# ArticulatedPCBContactBoard.net
KiCad netlist of a schematic drawn in EAGLE
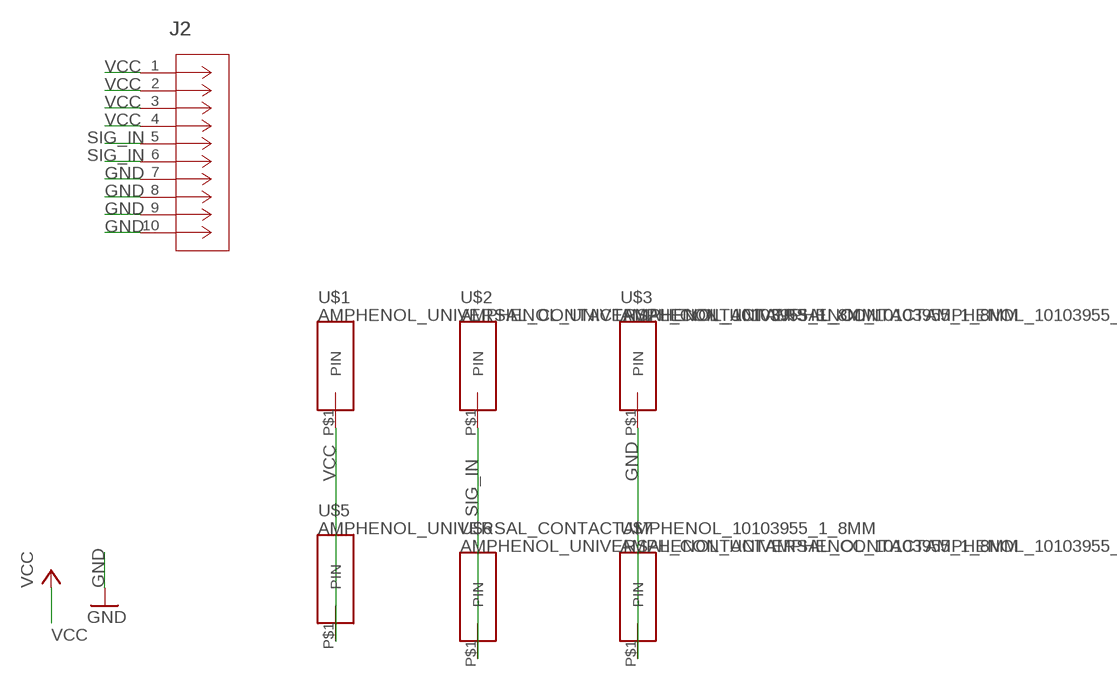
[diagram p0: schematic, sheet 1]

(export (version "E")
  (design (tool "Eeschema 10.0.6"))
  (components
    (comp (ref "J2")
      (value "DF23C-10DS-0.5V(51)")
      (footprint "eagle-import:CONN_DF23C-10DS-0.5V(51)_HIR")
      (fields (field (name "COPYRIGHT") "Copyright (C) 2018 Accelerated Designs. All rights reserved"))
      (libsource (lib "eagle-import") (part "DF23C-10DS-0.5V(51)"))
    )
    (comp (ref "U$1")
      (value "AMPHENOL_UNIVERSAL_CONTACTAMPHENOL_10103955_1_8MM")
      (footprint "eagle-import:AMPHENOL10103955")
      (libsource (lib "eagle-import") (part "AMPHENOL_UNIVERSAL_CONTACTAMPHENOL_10103955_1_8MM"))
    )
    (comp (ref "U$2")
      (value "AMPHENOL_UNIVERSAL_CONTACTAMPHENOL_10103955_1_8MM")
      (footprint "eagle-import:AMPHENOL10103955")
      (libsource (lib "eagle-import") (part "AMPHENOL_UNIVERSAL_CONTACTAMPHENOL_10103955_1_8MM"))
    )
    (comp (ref "U$3")
      (value "AMPHENOL_UNIVERSAL_CONTACTAMPHENOL_10103955_1_8MM")
      (footprint "eagle-import:AMPHENOL10103955")
      (libsource (lib "eagle-import") (part "AMPHENOL_UNIVERSAL_CONTACTAMPHENOL_10103955_1_8MM"))
    )
    (comp (ref "U$5")
      (value "AMPHENOL_UNIVERSAL_CONTACTAMPHENOL_10103955_1_8MM")
      (footprint "eagle-import:AMPHENOL10103955")
      (libsource (lib "eagle-import") (part "AMPHENOL_UNIVERSAL_CONTACTAMPHENOL_10103955_1_8MM"))
    )
    (comp (ref "U$6")
      (value "AMPHENOL_UNIVERSAL_CONTACTAMPHENOL_10103955_1_8MM")
      (footprint "eagle-import:AMPHENOL10103955")
      (libsource (lib "eagle-import") (part "AMPHENOL_UNIVERSAL_CONTACTAMPHENOL_10103955_1_8MM"))
    )
    (comp (ref "U$7")
      (value "AMPHENOL_UNIVERSAL_CONTACTAMPHENOL_10103955_1_8MM")
      (footprint "eagle-import:AMPHENOL10103955")
      (libsource (lib "eagle-import") (part "AMPHENOL_UNIVERSAL_CONTACTAMPHENOL_10103955_1_8MM"))
    )
  )
  (nets
    (net (code "1") (name "/SIG_IN") (class "Default")
      (node (ref "J2") (pin "5") (pinfunction "5_5") (pintype "passive"))
      (node (ref "J2") (pin "6") (pinfunction "6_6") (pintype "passive"))
      (node (ref "U$2") (pin "P$1") (pinfunction "PIN_P$1") (pintype "bidirectional"))
      (node (ref "U$6") (pin "P$1") (pinfunction "PIN_P$1") (pintype "bidirectional"))
    )
    (net (code "2") (name "GND") (class "Default")
      (node (ref "J2") (pin "10") (pinfunction "10_10") (pintype "passive"))
      (node (ref "J2") (pin "7") (pinfunction "7_7") (pintype "passive"))
      (node (ref "J2") (pin "8") (pinfunction "8_8") (pintype "passive"))
      (node (ref "J2") (pin "9") (pinfunction "9_9") (pintype "passive"))
      (node (ref "U$3") (pin "P$1") (pinfunction "PIN_P$1") (pintype "bidirectional"))
      (node (ref "U$7") (pin "P$1") (pinfunction "PIN_P$1") (pintype "bidirectional"))
    )
    (net (code "3") (name "VCC") (class "Default")
      (node (ref "J2") (pin "1") (pinfunction "1_1") (pintype "passive"))
      (node (ref "J2") (pin "2") (pinfunction "2_2") (pintype "passive"))
      (node (ref "J2") (pin "3") (pinfunction "3_3") (pintype "passive"))
      (node (ref "J2") (pin "4") (pinfunction "4_4") (pintype "passive"))
      (node (ref "U$1") (pin "P$1") (pinfunction "PIN_P$1") (pintype "bidirectional"))
      (node (ref "U$5") (pin "P$1") (pinfunction "PIN_P$1") (pintype "bidirectional"))
    )
  )
)
